# Shelf_System_F.net
KiCad netlist of a schematic drawn in Altium Designer
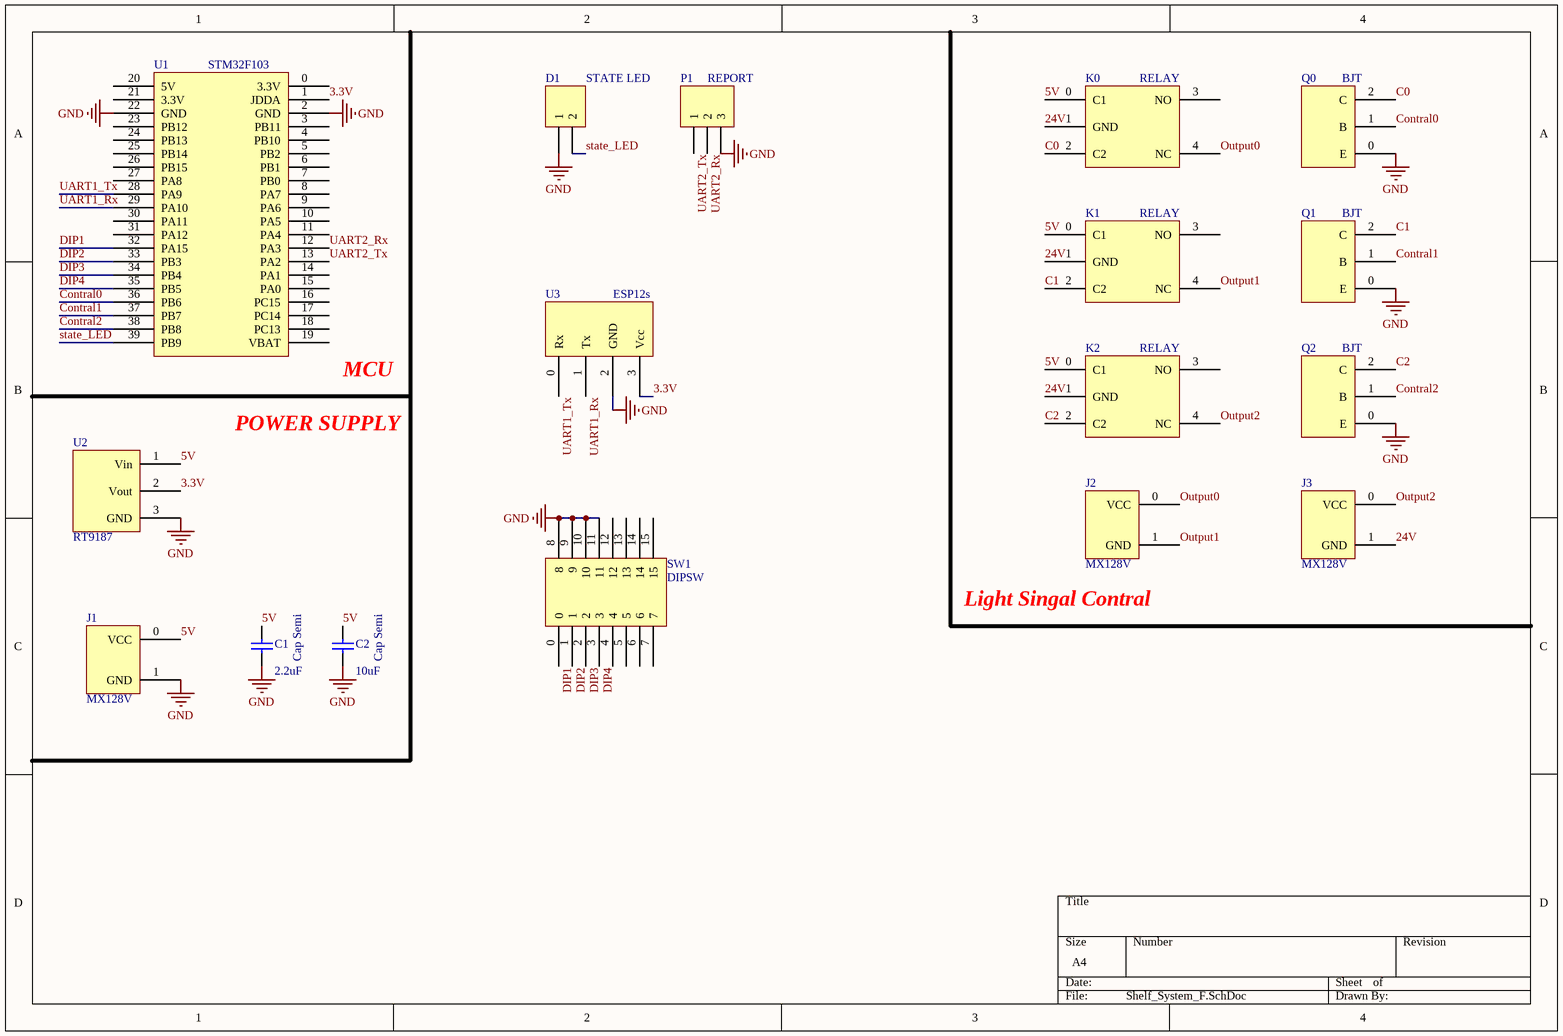
[diagram p0: Shelf_System_F.SchDoc]

(export (version "E")
  (design (tool "Eeschema 10.0.6"))
  (components
    (comp (ref "C1")
      (value "Cap Semi")
      (footprint "1608[0603]")
      (description "Capacitor (Semiconductor SIM Model)")
      (fields (field (name "ALTIUM_VALUE") "2.2uF") (field (name "PUBLISHER") "Altium Limited"))
      (libsource (lib "Miscellaneous Devices") (part "Cap Semi"))
    )
    (comp (ref "C2")
      (value "Cap Semi")
      (footprint "1608[0603]")
      (description "Capacitor (Semiconductor SIM Model)")
      (fields (field (name "ALTIUM_VALUE") "10uF") (field (name "PUBLISHER") "Altium Limited"))
      (libsource (lib "Miscellaneous Devices") (part "Cap Semi"))
    )
    (comp (ref "D1")
      (value "STATE LED")
      (footprint "HDR1X2")
      (description "Header, 2-Pin")
      (fields (field (name "PUBLISHER") "Altium Limited"))
      (libsource (lib "Miscellaneous Connectors") (part "Header 2"))
    )
    (comp (ref "J1") (value "MX128V") (footprint "MX128V") (libsource (lib "shelf_LIB") (part "MX128V")))
    (comp (ref "J2") (value "MX128V") (footprint "MX128V") (libsource (lib "shelf_LIB") (part "MX128V")))
    (comp (ref "J3") (value "MX128V") (footprint "MX128V") (libsource (lib "shelf_LIB") (part "MX128V")))
    (comp (ref "K0") (value "RELAY") (footprint "RELAY") (libsource (lib "shelf_LIB") (part "RELAY")))
    (comp (ref "K1") (value "RELAY") (footprint "RELAY") (libsource (lib "shelf_LIB") (part "RELAY")))
    (comp (ref "K2") (value "RELAY") (footprint "RELAY") (libsource (lib "shelf_LIB") (part "RELAY")))
    (comp (ref "P1")
      (value "REPORT")
      (footprint "HDR1X3")
      (description "Header, 3-Pin")
      (fields (field (name "PUBLISHER") "Altium Limited"))
      (libsource (lib "Miscellaneous Connectors") (part "Header 3"))
    )
    (comp (ref "Q0") (value "BJT") (footprint "bjt") (libsource (lib "shelf_LIB") (part "BJT")))
    (comp (ref "Q1") (value "BJT") (footprint "bjt") (libsource (lib "shelf_LIB") (part "BJT")))
    (comp (ref "Q2") (value "BJT") (footprint "bjt") (libsource (lib "shelf_LIB") (part "BJT")))
    (comp (ref "SW1") (value "DIPSW") (footprint "DIPSW") (libsource (lib "shelf_LIB") (part "DIPSW")))
    (comp (ref "U1")
      (value "STM32F103")
      (footprint "STM32F103")
      (libsource (lib "shelf_LIB") (part "STM32F103"))
    )
    (comp (ref "U2") (value "RT9187") (footprint "RT9187") (libsource (lib "shelf_LIB") (part "RT9187")))
    (comp (ref "U3") (value "ESP12s") (footprint "ESP12s") (libsource (lib "shelf_LIB") (part "ESP12s")))
  )
  (nets
    (net (code "1") (name "/3.3V") (class "Default")
      (node (ref "U1") (pin "1") (pinfunction "JDDA_1") (pintype "passive"))
      (node (ref "U2") (pin "2") (pinfunction "Vout_2") (pintype "passive"))
      (node (ref "U3") (pin "3") (pinfunction "Vcc_3") (pintype "passive"))
    )
    (net (code "2") (name "/5V") (class "Default")
      (node (ref "C1") (pin "2") (pinfunction "2_2") (pintype "passive"))
      (node (ref "C2") (pin "2") (pinfunction "2_2") (pintype "passive"))
      (node (ref "J1") (pin "0") (pinfunction "VCC_0") (pintype "passive"))
      (node (ref "K0") (pin "0") (pinfunction "C1_0") (pintype "passive"))
      (node (ref "K1") (pin "0") (pinfunction "C1_0") (pintype "passive"))
      (node (ref "K2") (pin "0") (pinfunction "C1_0") (pintype "passive"))
      (node (ref "U2") (pin "1") (pinfunction "Vin_1") (pintype "passive"))
    )
    (net (code "3") (name "/24V") (class "Default")
      (node (ref "J3") (pin "1") (pinfunction "GND_1") (pintype "passive"))
      (node (ref "K0") (pin "1") (pinfunction "GND_1") (pintype "passive"))
      (node (ref "K1") (pin "1") (pinfunction "GND_1") (pintype "passive"))
      (node (ref "K2") (pin "1") (pinfunction "GND_1") (pintype "passive"))
    )
    (net (code "4") (name "/C0") (class "Default")
      (node (ref "K0") (pin "2") (pinfunction "C2_2") (pintype "passive"))
      (node (ref "Q0") (pin "2") (pinfunction "C_2") (pintype "passive"))
    )
    (net (code "5") (name "/C1") (class "Default")
      (node (ref "K1") (pin "2") (pinfunction "C2_2") (pintype "passive"))
      (node (ref "Q1") (pin "2") (pinfunction "C_2") (pintype "passive"))
    )
    (net (code "6") (name "/C2") (class "Default")
      (node (ref "K2") (pin "2") (pinfunction "C2_2") (pintype "passive"))
      (node (ref "Q2") (pin "2") (pinfunction "C_2") (pintype "passive"))
    )
    (net (code "7") (name "/Contral0") (class "Default")
      (node (ref "Q0") (pin "1") (pinfunction "B_1") (pintype "passive"))
      (node (ref "U1") (pin "36") (pinfunction "PB6_36") (pintype "passive"))
    )
    (net (code "8") (name "/Contral1") (class "Default")
      (node (ref "Q1") (pin "1") (pinfunction "B_1") (pintype "passive"))
      (node (ref "U1") (pin "37") (pinfunction "PB7_37") (pintype "passive"))
    )
    (net (code "9") (name "/Contral2") (class "Default")
      (node (ref "Q2") (pin "1") (pinfunction "B_1") (pintype "passive"))
      (node (ref "U1") (pin "38") (pinfunction "PB8_38") (pintype "passive"))
    )
    (net (code "10") (name "/DIP1") (class "Default")
      (node (ref "SW1") (pin "0") (pinfunction "0_0") (pintype "passive"))
      (node (ref "U1") (pin "32") (pinfunction "PA15_32") (pintype "passive"))
    )
    (net (code "11") (name "/DIP2") (class "Default")
      (node (ref "SW1") (pin "1") (pinfunction "1_1") (pintype "passive"))
      (node (ref "U1") (pin "33") (pinfunction "PB3_33") (pintype "passive"))
    )
    (net (code "12") (name "/DIP3") (class "Default")
      (node (ref "SW1") (pin "2") (pinfunction "2_2") (pintype "passive"))
      (node (ref "U1") (pin "34") (pinfunction "PB4_34") (pintype "passive"))
    )
    (net (code "13") (name "/DIP4") (class "Default")
      (node (ref "SW1") (pin "3") (pinfunction "3_3") (pintype "passive"))
      (node (ref "U1") (pin "35") (pinfunction "PB5_35") (pintype "passive"))
    )
    (net (code "14") (name "/Output0") (class "Default")
      (node (ref "J2") (pin "0") (pinfunction "VCC_0") (pintype "passive"))
      (node (ref "K0") (pin "4") (pinfunction "NC_4") (pintype "passive"))
    )
    (net (code "15") (name "/Output1") (class "Default")
      (node (ref "J2") (pin "1") (pinfunction "GND_1") (pintype "passive"))
      (node (ref "K1") (pin "4") (pinfunction "NC_4") (pintype "passive"))
    )
    (net (code "16") (name "/Output2") (class "Default")
      (node (ref "J3") (pin "0") (pinfunction "VCC_0") (pintype "passive"))
      (node (ref "K2") (pin "4") (pinfunction "NC_4") (pintype "passive"))
    )
    (net (code "17") (name "/UART1_Rx") (class "Default")
      (node (ref "U1") (pin "29") (pinfunction "PA10_29") (pintype "passive"))
      (node (ref "U3") (pin "1") (pinfunction "Tx_1") (pintype "passive"))
    )
    (net (code "18") (name "/UART1_Tx") (class "Default")
      (node (ref "U1") (pin "28") (pinfunction "PA9_28") (pintype "passive"))
      (node (ref "U3") (pin "0") (pinfunction "Rx_0") (pintype "passive"))
    )
    (net (code "19") (name "/UART2_Rx") (class "Default")
      (node (ref "P1") (pin "2") (pinfunction "2_2") (pintype "passive"))
      (node (ref "U1") (pin "12") (pinfunction "PA3_12") (pintype "passive"))
    )
    (net (code "20") (name "/UART2_Tx") (class "Default")
      (node (ref "P1") (pin "1") (pinfunction "1_1") (pintype "passive"))
      (node (ref "U1") (pin "13") (pinfunction "PA2_13") (pintype "passive"))
    )
    (net (code "21") (name "/state_LED") (class "Default")
      (node (ref "D1") (pin "2") (pinfunction "2_2") (pintype "passive"))
      (node (ref "U1") (pin "39") (pinfunction "PB9_39") (pintype "passive"))
    )
    (net (code "22") (name "GND") (class "Default")
      (node (ref "C1") (pin "1") (pinfunction "1_1") (pintype "passive"))
      (node (ref "C2") (pin "1") (pinfunction "1_1") (pintype "passive"))
      (node (ref "D1") (pin "1") (pinfunction "1_1") (pintype "passive"))
      (node (ref "J1") (pin "1") (pinfunction "GND_1") (pintype "passive"))
      (node (ref "P1") (pin "3") (pinfunction "3_3") (pintype "passive"))
      (node (ref "Q0") (pin "0") (pinfunction "E_0") (pintype "passive"))
      (node (ref "Q1") (pin "0") (pinfunction "E_0") (pintype "passive"))
      (node (ref "Q2") (pin "0") (pinfunction "E_0") (pintype "passive"))
      (node (ref "SW1") (pin "10") (pinfunction "10_10") (pintype "passive"))
      (node (ref "SW1") (pin "11") (pinfunction "11_11") (pintype "passive"))
      (node (ref "SW1") (pin "8") (pinfunction "8_8") (pintype "passive"))
      (node (ref "SW1") (pin "9") (pinfunction "9_9") (pintype "passive"))
      (node (ref "U1") (pin "2") (pinfunction "GND_2") (pintype "passive"))
      (node (ref "U1") (pin "22") (pinfunction "GND_22") (pintype "passive"))
      (node (ref "U2") (pin "3") (pinfunction "GND_3") (pintype "passive"))
      (node (ref "U3") (pin "2") (pinfunction "GND_2") (pintype "passive"))
    )
    (net (code "23") (name "unconnected-(K0-NO-Pad3)") (class "Default")
      (node (ref "K0") (pin "3") (pinfunction "NO_3") (pintype "passive"))
    )
    (net (code "24") (name "unconnected-(K1-NO-Pad3)") (class "Default")
      (node (ref "K1") (pin "3") (pinfunction "NO_3") (pintype "passive"))
    )
    (net (code "25") (name "unconnected-(K2-NO-Pad3)") (class "Default")
      (node (ref "K2") (pin "3") (pinfunction "NO_3") (pintype "passive"))
    )
    (net (code "26") (name "unconnected-(SW1-Pad4)") (class "Default")
      (node (ref "SW1") (pin "4") (pinfunction "4_4") (pintype "passive"))
    )
    (net (code "27") (name "unconnected-(SW1-Pad5)") (class "Default")
      (node (ref "SW1") (pin "5") (pinfunction "5_5") (pintype "passive"))
    )
    (net (code "28") (name "unconnected-(SW1-Pad6)") (class "Default")
      (node (ref "SW1") (pin "6") (pinfunction "6_6") (pintype "passive"))
    )
    (net (code "29") (name "unconnected-(SW1-Pad7)") (class "Default")
      (node (ref "SW1") (pin "7") (pinfunction "7_7") (pintype "passive"))
    )
    (net (code "30") (name "unconnected-(SW1-Pad12)") (class "Default")
      (node (ref "SW1") (pin "12") (pinfunction "12_12") (pintype "passive"))
    )
    (net (code "31") (name "unconnected-(SW1-Pad13)") (class "Default")
      (node (ref "SW1") (pin "13") (pinfunction "13_13") (pintype "passive"))
    )
    (net (code "32") (name "unconnected-(SW1-Pad14)") (class "Default")
      (node (ref "SW1") (pin "14") (pinfunction "14_14") (pintype "passive"))
    )
    (net (code "33") (name "unconnected-(SW1-Pad15)") (class "Default")
      (node (ref "SW1") (pin "15") (pinfunction "15_15") (pintype "passive"))
    )
    (net (code "34") (name "unconnected-(U1-3.3V-Pad0)") (class "Default")
      (node (ref "U1") (pin "0") (pinfunction "3.3V_0") (pintype "passive"))
    )
    (net (code "35") (name "unconnected-(U1-3.3V-Pad21)") (class "Default")
      (node (ref "U1") (pin "21") (pinfunction "3.3V_21") (pintype "passive"))
    )
    (net (code "36") (name "unconnected-(U1-5V-Pad20)") (class "Default")
      (node (ref "U1") (pin "20") (pinfunction "5V_20") (pintype "passive"))
    )
    (net (code "37") (name "unconnected-(U1-PA0-Pad15)") (class "Default")
      (node (ref "U1") (pin "15") (pinfunction "PA0_15") (pintype "passive"))
    )
    (net (code "38") (name "unconnected-(U1-PA1-Pad14)") (class "Default")
      (node (ref "U1") (pin "14") (pinfunction "PA1_14") (pintype "passive"))
    )
    (net (code "39") (name "unconnected-(U1-PA4-Pad11)") (class "Default")
      (node (ref "U1") (pin "11") (pinfunction "PA4_11") (pintype "passive"))
    )
    (net (code "40") (name "unconnected-(U1-PA5-Pad10)") (class "Default")
      (node (ref "U1") (pin "10") (pinfunction "PA5_10") (pintype "passive"))
    )
    (net (code "41") (name "unconnected-(U1-PA6-Pad9)") (class "Default")
      (node (ref "U1") (pin "9") (pinfunction "PA6_9") (pintype "passive"))
    )
    (net (code "42") (name "unconnected-(U1-PA7-Pad8)") (class "Default")
      (node (ref "U1") (pin "8") (pinfunction "PA7_8") (pintype "passive"))
    )
    (net (code "43") (name "unconnected-(U1-PA8-Pad27)") (class "Default")
      (node (ref "U1") (pin "27") (pinfunction "PA8_27") (pintype "passive"))
    )
    (net (code "44") (name "unconnected-(U1-PA11-Pad30)") (class "Default")
      (node (ref "U1") (pin "30") (pinfunction "PA11_30") (pintype "passive"))
    )
    (net (code "45") (name "unconnected-(U1-PA12-Pad31)") (class "Default")
      (node (ref "U1") (pin "31") (pinfunction "PA12_31") (pintype "passive"))
    )
    (net (code "46") (name "unconnected-(U1-PB0-Pad7)") (class "Default")
      (node (ref "U1") (pin "7") (pinfunction "PB0_7") (pintype "passive"))
    )
    (net (code "47") (name "unconnected-(U1-PB1-Pad6)") (class "Default")
      (node (ref "U1") (pin "6") (pinfunction "PB1_6") (pintype "passive"))
    )
    (net (code "48") (name "unconnected-(U1-PB2-Pad5)") (class "Default")
      (node (ref "U1") (pin "5") (pinfunction "PB2_5") (pintype "passive"))
    )
    (net (code "49") (name "unconnected-(U1-PB10-Pad4)") (class "Default")
      (node (ref "U1") (pin "4") (pinfunction "PB10_4") (pintype "passive"))
    )
    (net (code "50") (name "unconnected-(U1-PB11-Pad3)") (class "Default")
      (node (ref "U1") (pin "3") (pinfunction "PB11_3") (pintype "passive"))
    )
    (net (code "51") (name "unconnected-(U1-PB12-Pad23)") (class "Default")
      (node (ref "U1") (pin "23") (pinfunction "PB12_23") (pintype "passive"))
    )
    (net (code "52") (name "unconnected-(U1-PB13-Pad24)") (class "Default")
      (node (ref "U1") (pin "24") (pinfunction "PB13_24") (pintype "passive"))
    )
    (net (code "53") (name "unconnected-(U1-PB14-Pad25)") (class "Default")
      (node (ref "U1") (pin "25") (pinfunction "PB14_25") (pintype "passive"))
    )
    (net (code "54") (name "unconnected-(U1-PB15-Pad26)") (class "Default")
      (node (ref "U1") (pin "26") (pinfunction "PB15_26") (pintype "passive"))
    )
    (net (code "55") (name "unconnected-(U1-PC13-Pad18)") (class "Default")
      (node (ref "U1") (pin "18") (pinfunction "PC13_18") (pintype "passive"))
    )
    (net (code "56") (name "unconnected-(U1-PC14-Pad17)") (class "Default")
      (node (ref "U1") (pin "17") (pinfunction "PC14_17") (pintype "passive"))
    )
    (net (code "57") (name "unconnected-(U1-PC15-Pad16)") (class "Default")
      (node (ref "U1") (pin "16") (pinfunction "PC15_16") (pintype "passive"))
    )
    (net (code "58") (name "unconnected-(U1-VBAT-Pad19)") (class "Default")
      (node (ref "U1") (pin "19") (pinfunction "VBAT_19") (pintype "passive"))
    )
  )
)
